# sd_debug.net
KiCad netlist of a schematic drawn in Altium Designer
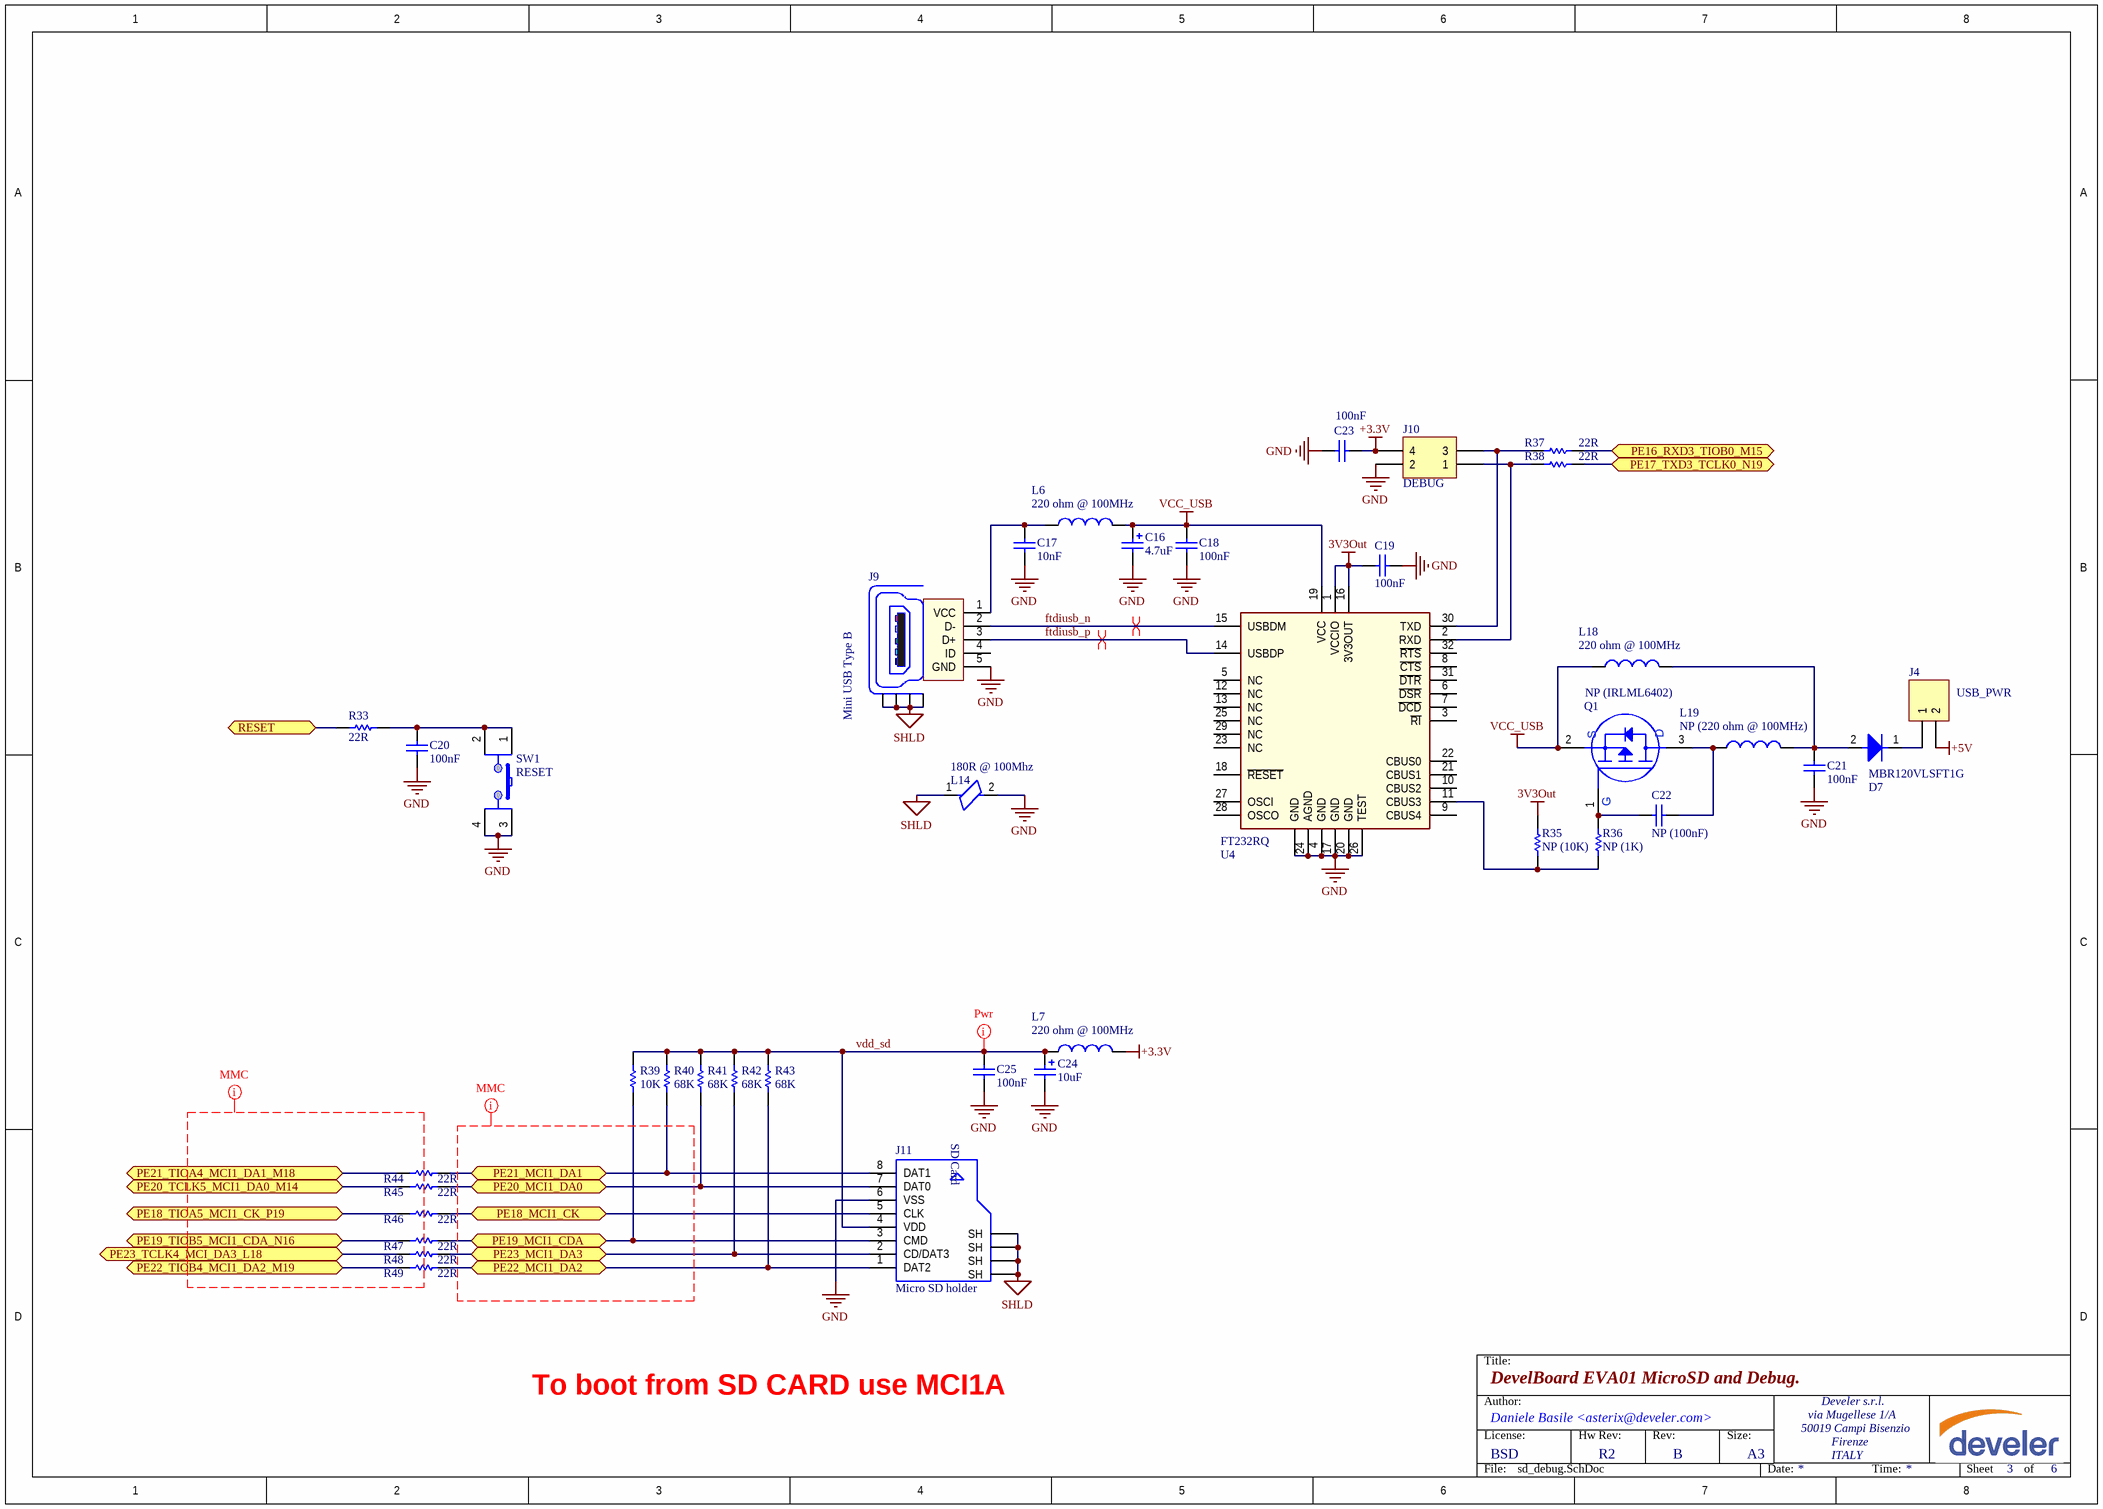
[diagram p0: sd_debug.SchDoc]

(export (version "E")
  (design (tool "Eeschema 10.0.6"))
  (components
    (comp (ref "C16")
      (value "4.7uF")
      (footprint "1206_[3216]")
      (description "Ceramic X5R 25V")
      (fields (field (name "PUBLISHER") "Altium Limited"))
      (libsource (lib "DEVELER_Library") (part "Cap Pol1"))
    )
    (comp (ref "C17")
      (value "10nF")
      (footprint "0603_[1608]")
      (description "Ceramic X7R 50V")
      (fields (field (name "PUBLISHER") "Altium Limited"))
      (libsource (lib "DEVELER_Library") (part "Cap"))
    )
    (comp (ref "C18")
      (value "100nF")
      (footprint "0603_[1608]")
      (description "Ceramic X7R 50V")
      (fields (field (name "PUBLISHER") "Altium Limited"))
      (libsource (lib "DEVELER_Library") (part "Cap"))
    )
    (comp (ref "C19")
      (value "100nF")
      (footprint "0603_[1608]")
      (description "Ceramic X7R 50V")
      (fields (field (name "PUBLISHER") "Altium Limited"))
      (libsource (lib "DEVELER_Library") (part "Cap"))
    )
    (comp (ref "C20")
      (value "100nF")
      (footprint "0603_[1608]")
      (description "Ceramic X7R 50V")
      (fields (field (name "PUBLISHER") "Altium Limited"))
      (libsource (lib "DEVELER_Library") (part "Cap"))
    )
    (comp (ref "C21")
      (value "100nF")
      (footprint "0603_[1608]")
      (description "Ceramic X7R 50V")
      (fields (field (name "PUBLISHER") "Altium Limited"))
      (libsource (lib "DEVELER_Library") (part "Cap"))
    )
    (comp (ref "C22")
      (value "NP (100nF)")
      (footprint "0603_[1608]")
      (description "Ceramic X7R 50V")
      (fields (field (name "PUBLISHER") "Altium Limited"))
      (libsource (lib "DEVELER_Library") (part "Cap"))
    )
    (comp (ref "C23")
      (value "100nF")
      (footprint "0603_[1608]")
      (description "Ceramic X7R 50V")
      (fields (field (name "PUBLISHER") "Altium Limited"))
      (libsource (lib "DEVELER_Library") (part "Cap"))
    )
    (comp (ref "C24")
      (value "10uF")
      (footprint "1206_[3216]")
      (description "Ceramic X5R 25V")
      (fields (field (name "PUBLISHER") "Altium Limited"))
      (libsource (lib "DEVELER_Library") (part "Cap Pol1"))
    )
    (comp (ref "C25")
      (value "100nF")
      (footprint "0603_[1608]")
      (description "Ceramic X7R 50V")
      (fields (field (name "PUBLISHER") "Altium Limited"))
      (libsource (lib "Miscellaneous Devices") (part "Cap"))
    )
    (comp (ref "D7")
      (value "MBR120VLSFT1G")
      (footprint "SOD-123")
      (description "Diode Schottky  low Vf, If 1A (PMEG3010ER; MBRX120LF)")
      (libsource (lib "DEVELER_Library") (part "Diode"))
    )
    (comp (ref "J4")
      (value "USB_PWR")
      (footprint "HEADER_1X2_2.54MM_THD")
      (description "Pin Header, 2pin, 1x2, 2.54mm, THD")
      (fields (field (name "PUBLISHER") "Altium Limited"))
      (libsource (lib "Miscellaneous Connectors") (part "Header 2"))
    )
    (comp (ref "J9")
      (value "Mini USB Type B")
      (footprint "usb_typeB_mini_smd")
      (description "Mini USB SMT Type B 5 Contacts (WE 65100516121)")
      (fields
        (field (name "MANUFACTURER") "Würth Elektronik eiSos GmbH")
        (field (name "PARTNO") "65100516121")
        (field (name "CREATED BY") "Karrer Zheng")
      )
      (libsource (lib "DEVELER_Library") (part "USB_Con_Type_B_mini_SMT"))
    )
    (comp (ref "J10")
      (value "DEBUG")
      (footprint "HEADER_2X2_2.54MM_THD")
      (description "Pin Header, 4pin, 2x2, 2.54mm, THD")
      (fields (field (name "PUBLISHER") "Altium Limited"))
      (libsource (lib "Miscellaneous Connectors") (part "Header 2X2"))
    )
    (comp (ref "J11")
      (value "Micro SD holder")
      (footprint "micro_sd_holder_pp")
      (description "WR-CRD Micro SD_Push and Push (693071010811)")
      (fields
        (field (name "MANUFACTURER") "Würth Elektronik eiSos GmbH")
        (field (name "PARTNO") "693071010811")
        (field (name "CREATED BY") "Karrer Zheng")
      )
      (libsource (lib "DEVELER_Library") (part "micro_sd_holde"))
    )
    (comp (ref "L6")
      (value "220 ohm @ 100MHz")
      (footprint "0805_[2012]")
      (description "Ferrite Beat (WE 742792022)")
      (libsource (lib "DEVELER_Library") (part "Inductor"))
    )
    (comp (ref "L7")
      (value "220 ohm @ 100MHz")
      (footprint "0805_[2012]")
      (description "Ferrite Beat (WE 742792022)")
      (libsource (lib "DEVELER_Library") (part "Inductor"))
    )
    (comp (ref "L14")
      (value "180R @ 100Mhz")
      (footprint "0603_[1608]")
      (description "Ferrite Beat (WE 7427927218)")
      (libsource (lib "project42_lib") (part "BEAD_ FERRITE"))
    )
    (comp (ref "L18")
      (value "220 ohm @ 100MHz")
      (footprint "0805_[2012]")
      (description "Ferrite Beat (WE 742792022)")
      (libsource (lib "DEVELER_Library") (part "Inductor"))
    )
    (comp (ref "L19")
      (value "NP (220 ohm @ 100MHz)")
      (footprint "0805_[2012]")
      (description "Ferrite Beat (WE 742792022)")
      (libsource (lib "DEVELER_Library") (part "Inductor"))
    )
    (comp (ref "Q1")
      (value "NP (IRLML6402)")
      (footprint "SOT-23")
      (description "Mos N Channel")
      (libsource (lib "DEVELER_Library") (part "MOSFET-P 3pin"))
    )
    (comp (ref "R33")
      (value "22R")
      (footprint "0603_[1608]")
      (description "Resistor")
      (fields (field (name "PUBLISHER") "Altium Limited"))
      (libsource (lib "DEVELER_Library") (part "Res1"))
    )
    (comp (ref "R35")
      (value "NP (10K)")
      (footprint "0603_[1608]")
      (description "Resistor")
      (fields (field (name "PUBLISHER") "Altium Limited"))
      (libsource (lib "DEVELER_Library") (part "Res1"))
    )
    (comp (ref "R36")
      (value "NP (1K)")
      (footprint "0603_[1608]")
      (description "Resistor")
      (fields (field (name "PUBLISHER") "Altium Limited"))
      (libsource (lib "DEVELER_Library") (part "Res1"))
    )
    (comp (ref "R37")
      (value "22R")
      (footprint "0603_[1608]")
      (description "Resistor")
      (fields (field (name "PUBLISHER") "Altium Limited"))
      (libsource (lib "DEVELER_Library") (part "Res1"))
    )
    (comp (ref "R38")
      (value "22R")
      (footprint "0603_[1608]")
      (description "Resistor")
      (fields (field (name "PUBLISHER") "Altium Limited"))
      (libsource (lib "DEVELER_Library") (part "Res1"))
    )
    (comp (ref "R39")
      (value "10K")
      (footprint "0603_[1608]")
      (description "Resistor")
      (fields (field (name "PUBLISHER") "Altium Limited"))
      (libsource (lib "DEVELER_Library") (part "Res1"))
    )
    (comp (ref "R40")
      (value "68K")
      (footprint "0603_[1608]")
      (description "Resistor")
      (fields (field (name "PUBLISHER") "Altium Limited"))
      (libsource (lib "DEVELER_Library") (part "Res1"))
    )
    (comp (ref "R41")
      (value "68K")
      (footprint "0603_[1608]")
      (description "Resistor")
      (fields (field (name "PUBLISHER") "Altium Limited"))
      (libsource (lib "DEVELER_Library") (part "Res1"))
    )
    (comp (ref "R42")
      (value "68K")
      (footprint "0603_[1608]")
      (description "Resistor")
      (fields (field (name "PUBLISHER") "Altium Limited"))
      (libsource (lib "DEVELER_Library") (part "Res1"))
    )
    (comp (ref "R43")
      (value "68K")
      (footprint "0603_[1608]")
      (description "Resistor")
      (fields (field (name "PUBLISHER") "Altium Limited"))
      (libsource (lib "DEVELER_Library") (part "Res1"))
    )
    (comp (ref "R44")
      (value "22R")
      (footprint "0603_[1608]")
      (description "Resistor")
      (fields (field (name "PUBLISHER") "Altium Limited"))
      (libsource (lib "DEVELER_Library") (part "Res1"))
    )
    (comp (ref "R45")
      (value "22R")
      (footprint "0603_[1608]")
      (description "Resistor")
      (fields (field (name "PUBLISHER") "Altium Limited"))
      (libsource (lib "DEVELER_Library") (part "Res1"))
    )
    (comp (ref "R46")
      (value "22R")
      (footprint "0603_[1608]")
      (description "Resistor")
      (fields (field (name "PUBLISHER") "Altium Limited"))
      (libsource (lib "DEVELER_Library") (part "Res1"))
    )
    (comp (ref "R47")
      (value "22R")
      (footprint "0603_[1608]")
      (description "Resistor")
      (fields (field (name "PUBLISHER") "Altium Limited"))
      (libsource (lib "DEVELER_Library") (part "Res1"))
    )
    (comp (ref "R48")
      (value "22R")
      (footprint "0603_[1608]")
      (description "Resistor")
      (fields (field (name "PUBLISHER") "Altium Limited"))
      (libsource (lib "DEVELER_Library") (part "Res1"))
    )
    (comp (ref "R49")
      (value "22R")
      (footprint "0603_[1608]")
      (description "Resistor")
      (fields (field (name "PUBLISHER") "Altium Limited"))
      (libsource (lib "DEVELER_Library") (part "Res1"))
    )
    (comp (ref "SW1")
      (value "RESET")
      (footprint "TACTILE_SWITCH_6x6MM_SMD")
      (description "Tactile switch smd H=4.3mm 10x6mm (like cod. Farnell 2435308)")
      (libsource (lib "DEVELER_Library") (part "tactile_switch"))
    )
    (comp (ref "U4")
      (value "FT232RQ")
      (footprint "QFN-32")
      (description "Serial TTL 232 <-> USB (QFN-32)")
      (libsource (lib "DEVELER_Library") (part "FT232RQ"))
    )
  )
  (nets
    (net (code "1") (name "+3.3V") (class "Default")
      (node (ref "C23") (pin "1") (pinfunction "1_1") (pintype "passive"))
      (node (ref "J10") (pin "4") (pinfunction "4_4") (pintype "passive"))
      (node (ref "L7") (pin "1") (pinfunction "1_1") (pintype "passive"))
    )
    (net (code "2") (name "+5V") (class "Default")
      (node (ref "J4") (pin "2") (pinfunction "2_2") (pintype "passive"))
    )
    (net (code "3") (name "/PE16_RXD3_TIOB0_M15") (class "Default")
      (node (ref "R37") (pin "1") (pinfunction "1_1") (pintype "passive"))
    )
    (net (code "4") (name "/PE17_TXD3_TCLK0_N19") (class "Default")
      (node (ref "R38") (pin "1") (pinfunction "1_1") (pintype "passive"))
    )
    (net (code "5") (name "/PE18_MCI1_CK") (class "Default")
      (node (ref "J11") (pin "5") (pinfunction "CLK_5") (pintype "passive"))
      (node (ref "R46") (pin "2") (pinfunction "2_2") (pintype "passive"))
    )
    (net (code "6") (name "/PE18_TIOA5_MCI1_CK_P19") (class "Default")
      (node (ref "R46") (pin "1") (pinfunction "1_1") (pintype "passive"))
    )
    (net (code "7") (name "/PE19_MCI1_CDA") (class "Default")
      (node (ref "J11") (pin "3") (pinfunction "CMD_3") (pintype "passive"))
      (node (ref "R39") (pin "2") (pinfunction "2_2") (pintype "passive"))
      (node (ref "R47") (pin "2") (pinfunction "2_2") (pintype "passive"))
    )
    (net (code "8") (name "/PE19_TIOB5_MCI1_CDA_N16") (class "Default")
      (node (ref "R47") (pin "1") (pinfunction "1_1") (pintype "passive"))
    )
    (net (code "9") (name "/PE20_MCI1_DA0") (class "Default")
      (node (ref "J11") (pin "7") (pinfunction "DAT0_7") (pintype "passive"))
      (node (ref "R41") (pin "2") (pinfunction "2_2") (pintype "passive"))
      (node (ref "R45") (pin "2") (pinfunction "2_2") (pintype "passive"))
    )
    (net (code "10") (name "/PE20_TCLK5_MCI1_DA0_M14") (class "Default")
      (node (ref "R45") (pin "1") (pinfunction "1_1") (pintype "passive"))
    )
    (net (code "11") (name "/PE21_MCI1_DA1") (class "Default")
      (node (ref "J11") (pin "8") (pinfunction "DAT1_8") (pintype "passive"))
      (node (ref "R40") (pin "2") (pinfunction "2_2") (pintype "passive"))
      (node (ref "R44") (pin "2") (pinfunction "2_2") (pintype "passive"))
    )
    (net (code "12") (name "/PE21_TIOA4_MCI1_DA1_M18") (class "Default")
      (node (ref "R44") (pin "1") (pinfunction "1_1") (pintype "passive"))
    )
    (net (code "13") (name "/PE22_MCI1_DA2") (class "Default")
      (node (ref "J11") (pin "1") (pinfunction "DAT2_1") (pintype "passive"))
      (node (ref "R43") (pin "2") (pinfunction "2_2") (pintype "passive"))
      (node (ref "R49") (pin "2") (pinfunction "2_2") (pintype "passive"))
    )
    (net (code "14") (name "/PE22_TIOB4_MCI1_DA2_M19") (class "Default")
      (node (ref "R49") (pin "1") (pinfunction "1_1") (pintype "passive"))
    )
    (net (code "15") (name "/PE23_MCI1_DA3") (class "Default")
      (node (ref "J11") (pin "2") (pinfunction "CD/DAT3_2") (pintype "passive"))
      (node (ref "R42") (pin "2") (pinfunction "2_2") (pintype "passive"))
      (node (ref "R48") (pin "2") (pinfunction "2_2") (pintype "passive"))
    )
    (net (code "16") (name "/PE23_TCLK4_MCI_DA3_L18") (class "Default")
      (node (ref "R48") (pin "1") (pinfunction "1_1") (pintype "passive"))
    )
    (net (code "17") (name "/RESET") (class "Default")
      (node (ref "R33") (pin "2") (pinfunction "2_2") (pintype "passive"))
    )
    (net (code "18") (name "/ftdiusb_n") (class "Default")
      (node (ref "J9") (pin "2") (pinfunction "D-_2") (pintype "passive"))
      (node (ref "U4") (pin "15") (pinfunction "USBDM_15") (pintype "passive"))
    )
    (net (code "19") (name "/ftdiusb_p") (class "Default")
      (node (ref "J9") (pin "3") (pinfunction "D+_3") (pintype "passive"))
      (node (ref "U4") (pin "14") (pinfunction "USBDP_14") (pintype "passive"))
    )
    (net (code "20") (name "/vdd_sd") (class "Default")
      (node (ref "C24") (pin "1") (pinfunction "1_1") (pintype "passive"))
      (node (ref "C25") (pin "1") (pinfunction "1_1") (pintype "passive"))
      (node (ref "J11") (pin "4") (pinfunction "VDD_4") (pintype "passive"))
      (node (ref "L7") (pin "2") (pinfunction "2_2") (pintype "passive"))
      (node (ref "R39") (pin "1") (pinfunction "1_1") (pintype "passive"))
      (node (ref "R40") (pin "1") (pinfunction "1_1") (pintype "passive"))
      (node (ref "R41") (pin "1") (pinfunction "1_1") (pintype "passive"))
      (node (ref "R42") (pin "1") (pinfunction "1_1") (pintype "passive"))
      (node (ref "R43") (pin "1") (pinfunction "1_1") (pintype "passive"))
    )
    (net (code "21") (name "3V3Out") (class "Default")
      (node (ref "C19") (pin "1") (pinfunction "1_1") (pintype "passive"))
      (node (ref "R35") (pin "1") (pinfunction "1_1") (pintype "passive"))
      (node (ref "U4") (pin "1") (pinfunction "VCCIO_1") (pintype "passive"))
      (node (ref "U4") (pin "16") (pinfunction "3V3OUT_16") (pintype "passive"))
    )
    (net (code "22") (name "GND") (class "Default")
      (node (ref "C16") (pin "2") (pinfunction "2_2") (pintype "passive"))
      (node (ref "C17") (pin "2") (pinfunction "2_2") (pintype "passive"))
      (node (ref "C18") (pin "2") (pinfunction "2_2") (pintype "passive"))
      (node (ref "C19") (pin "2") (pinfunction "2_2") (pintype "passive"))
      (node (ref "C20") (pin "1") (pinfunction "1_1") (pintype "passive"))
      (node (ref "C21") (pin "1") (pinfunction "1_1") (pintype "passive"))
      (node (ref "C23") (pin "2") (pinfunction "2_2") (pintype "passive"))
      (node (ref "C24") (pin "2") (pinfunction "2_2") (pintype "passive"))
      (node (ref "C25") (pin "2") (pinfunction "2_2") (pintype "passive"))
      (node (ref "J10") (pin "2") (pinfunction "2_2") (pintype "passive"))
      (node (ref "J11") (pin "6") (pinfunction "VSS_6") (pintype "passive"))
      (node (ref "J9") (pin "5") (pinfunction "GND_5") (pintype "passive"))
      (node (ref "L14") (pin "2") (pinfunction "2_2") (pintype "passive"))
      (node (ref "SW1") (pin "3") (pinfunction "3_3") (pintype "passive"))
      (node (ref "SW1") (pin "4") (pinfunction "4_4") (pintype "passive"))
      (node (ref "U4") (pin "17") (pinfunction "GND_17") (pintype "passive"))
      (node (ref "U4") (pin "20") (pinfunction "GND_20") (pintype "passive"))
      (node (ref "U4") (pin "24") (pinfunction "AGND_24") (pintype "passive"))
      (node (ref "U4") (pin "26") (pinfunction "TEST_26") (pintype "passive"))
      (node (ref "U4") (pin "4") (pinfunction "GND_4") (pintype "passive"))
      (node (ref "U4") (pin "GND_PAD") (pinfunction "GND_GND_PAD") (pintype "passive"))
    )
    (net (code "23") (name "Net-(C20-Pad2)") (class "Default")
      (node (ref "C20") (pin "2") (pinfunction "2_2") (pintype "passive"))
      (node (ref "R33") (pin "1") (pinfunction "1_1") (pintype "passive"))
      (node (ref "SW1") (pin "1") (pinfunction "1_1") (pintype "passive"))
      (node (ref "SW1") (pin "2") (pinfunction "2_2") (pintype "passive"))
    )
    (net (code "24") (name "Net-(D7-A)") (class "Default")
      (node (ref "C21") (pin "2") (pinfunction "2_2") (pintype "passive"))
      (node (ref "D7") (pin "2") (pinfunction "A_2") (pintype "passive"))
      (node (ref "L18") (pin "1") (pinfunction "1_1") (pintype "passive"))
      (node (ref "L19") (pin "1") (pinfunction "1_1") (pintype "passive"))
    )
    (net (code "25") (name "Net-(D7-K)") (class "Default")
      (node (ref "D7") (pin "1") (pinfunction "K_1") (pintype "passive"))
      (node (ref "J4") (pin "1") (pinfunction "1_1") (pintype "passive"))
    )
    (net (code "26") (name "Net-(J9-VCC)") (class "Default")
      (node (ref "C17") (pin "1") (pinfunction "1_1") (pintype "passive"))
      (node (ref "J9") (pin "1") (pinfunction "VCC_1") (pintype "passive"))
      (node (ref "L6") (pin "2") (pinfunction "2_2") (pintype "passive"))
    )
    (net (code "27") (name "Net-(Q1-D)") (class "Default")
      (node (ref "C22") (pin "2") (pinfunction "2_2") (pintype "passive"))
      (node (ref "L19") (pin "2") (pinfunction "2_2") (pintype "passive"))
      (node (ref "Q1") (pin "3") (pinfunction "D_3") (pintype "passive"))
    )
    (net (code "28") (name "Net-(Q1-G)") (class "Default")
      (node (ref "C22") (pin "1") (pinfunction "1_1") (pintype "passive"))
      (node (ref "Q1") (pin "1") (pinfunction "G_1") (pintype "passive"))
      (node (ref "R36") (pin "1") (pinfunction "1_1") (pintype "passive"))
    )
    (net (code "29") (name "Net-(U4-CBUS3)") (class "Default")
      (node (ref "R35") (pin "2") (pinfunction "2_2") (pintype "passive"))
      (node (ref "R36") (pin "2") (pinfunction "2_2") (pintype "passive"))
      (node (ref "U4") (pin "11") (pinfunction "CBUS3_11") (pintype "passive"))
    )
    (net (code "30") (name "Net-(U4-RXD)") (class "Default")
      (node (ref "J10") (pin "1") (pinfunction "1_1") (pintype "passive"))
      (node (ref "R38") (pin "2") (pinfunction "2_2") (pintype "passive"))
      (node (ref "U4") (pin "2") (pinfunction "RXD_2") (pintype "passive"))
    )
    (net (code "31") (name "Net-(U4-TXD)") (class "Default")
      (node (ref "J10") (pin "3") (pinfunction "3_3") (pintype "passive"))
      (node (ref "R37") (pin "2") (pinfunction "2_2") (pintype "passive"))
      (node (ref "U4") (pin "30") (pinfunction "TXD_30") (pintype "passive"))
    )
    (net (code "32") (name "SHLD") (class "Default")
      (node (ref "J11") (pin "Z1") (pinfunction "SH_Z1") (pintype "passive"))
      (node (ref "J11") (pin "Z2") (pinfunction "SH_Z2") (pintype "passive"))
      (node (ref "J11") (pin "Z3") (pinfunction "SH_Z3") (pintype "passive"))
      (node (ref "J11") (pin "Z4") (pinfunction "SH_Z4") (pintype "passive"))
      (node (ref "J9") (pin "Z1") (pinfunction "Shield_Z1") (pintype "passive"))
      (node (ref "J9") (pin "Z2") (pinfunction "Shield_Z2") (pintype "passive"))
      (node (ref "J9") (pin "Z3") (pinfunction "Shield_Z3") (pintype "passive"))
      (node (ref "J9") (pin "Z4") (pinfunction "Shield_Z4") (pintype "passive"))
      (node (ref "L14") (pin "1") (pinfunction "1_1") (pintype "passive"))
    )
    (net (code "33") (name "VCC_USB") (class "Default")
      (node (ref "C16") (pin "1") (pinfunction "1_1") (pintype "passive"))
      (node (ref "C18") (pin "1") (pinfunction "1_1") (pintype "passive"))
      (node (ref "L18") (pin "2") (pinfunction "2_2") (pintype "passive"))
      (node (ref "L6") (pin "1") (pinfunction "1_1") (pintype "passive"))
      (node (ref "Q1") (pin "2") (pinfunction "S_2") (pintype "passive"))
      (node (ref "U4") (pin "19") (pinfunction "VCC_19") (pintype "passive"))
    )
    (net (code "34") (name "unconnected-(J9-ID-Pad4)") (class "Default")
      (node (ref "J9") (pin "4") (pinfunction "ID_4") (pintype "passive"))
    )
    (net (code "35") (name "unconnected-(U4-CBUS0-Pad22)") (class "Default")
      (node (ref "U4") (pin "22") (pinfunction "CBUS0_22") (pintype "passive"))
    )
    (net (code "36") (name "unconnected-(U4-CBUS1-Pad21)") (class "Default")
      (node (ref "U4") (pin "21") (pinfunction "CBUS1_21") (pintype "passive"))
    )
    (net (code "37") (name "unconnected-(U4-CBUS2-Pad10)") (class "Default")
      (node (ref "U4") (pin "10") (pinfunction "CBUS2_10") (pintype "passive"))
    )
    (net (code "38") (name "unconnected-(U4-CBUS4-Pad9)") (class "Default")
      (node (ref "U4") (pin "9") (pinfunction "CBUS4_9") (pintype "passive"))
    )
    (net (code "39") (name "unconnected-(U4-NC-Pad5)") (class "Default")
      (node (ref "U4") (pin "5") (pinfunction "NC_5") (pintype "passive"))
    )
    (net (code "40") (name "unconnected-(U4-NC-Pad12)") (class "Default")
      (node (ref "U4") (pin "12") (pinfunction "NC_12") (pintype "passive"))
    )
    (net (code "41") (name "unconnected-(U4-NC-Pad13)") (class "Default")
      (node (ref "U4") (pin "13") (pinfunction "NC_13") (pintype "passive"))
    )
    (net (code "42") (name "unconnected-(U4-NC-Pad23)") (class "Default")
      (node (ref "U4") (pin "23") (pinfunction "NC_23") (pintype "passive"))
    )
    (net (code "43") (name "unconnected-(U4-NC-Pad25)") (class "Default")
      (node (ref "U4") (pin "25") (pinfunction "NC_25") (pintype "passive"))
    )
    (net (code "44") (name "unconnected-(U4-NC-Pad29)") (class "Default")
      (node (ref "U4") (pin "29") (pinfunction "NC_29") (pintype "passive"))
    )
    (net (code "45") (name "unconnected-(U4-OSCI-Pad27)") (class "Default")
      (node (ref "U4") (pin "27") (pinfunction "OSCI_27") (pintype "passive"))
    )
    (net (code "46") (name "unconnected-(U4-OSCO-Pad28)") (class "Default")
      (node (ref "U4") (pin "28") (pinfunction "OSCO_28") (pintype "passive"))
    )
    (net (code "47") (name "unconnected-(U4-~{CTS}-Pad8)") (class "Default")
      (node (ref "U4") (pin "8") (pinfunction "~{CTS}_8") (pintype "passive"))
    )
    (net (code "48") (name "unconnected-(U4-~{DCD}-Pad7)") (class "Default")
      (node (ref "U4") (pin "7") (pinfunction "~{DCD}_7") (pintype "passive"))
    )
    (net (code "49") (name "unconnected-(U4-~{DSR}-Pad6)") (class "Default")
      (node (ref "U4") (pin "6") (pinfunction "~{DSR}_6") (pintype "passive"))
    )
    (net (code "50") (name "unconnected-(U4-~{DTR}-Pad31)") (class "Default")
      (node (ref "U4") (pin "31") (pinfunction "~{DTR}_31") (pintype "passive"))
    )
    (net (code "51") (name "unconnected-(U4-~{RESET}-Pad18)") (class "Default")
      (node (ref "U4") (pin "18") (pinfunction "~{RESET}_18") (pintype "passive"))
    )
    (net (code "52") (name "unconnected-(U4-~{RI}-Pad3)") (class "Default")
      (node (ref "U4") (pin "3") (pinfunction "~{RI}_3") (pintype "passive"))
    )
    (net (code "53") (name "unconnected-(U4-~{RTS}-Pad32)") (class "Default")
      (node (ref "U4") (pin "32") (pinfunction "~{RTS}_32") (pintype "passive"))
    )
  )
)
